# motor_front.net
KiCad netlist of a schematic drawn in EAGLE
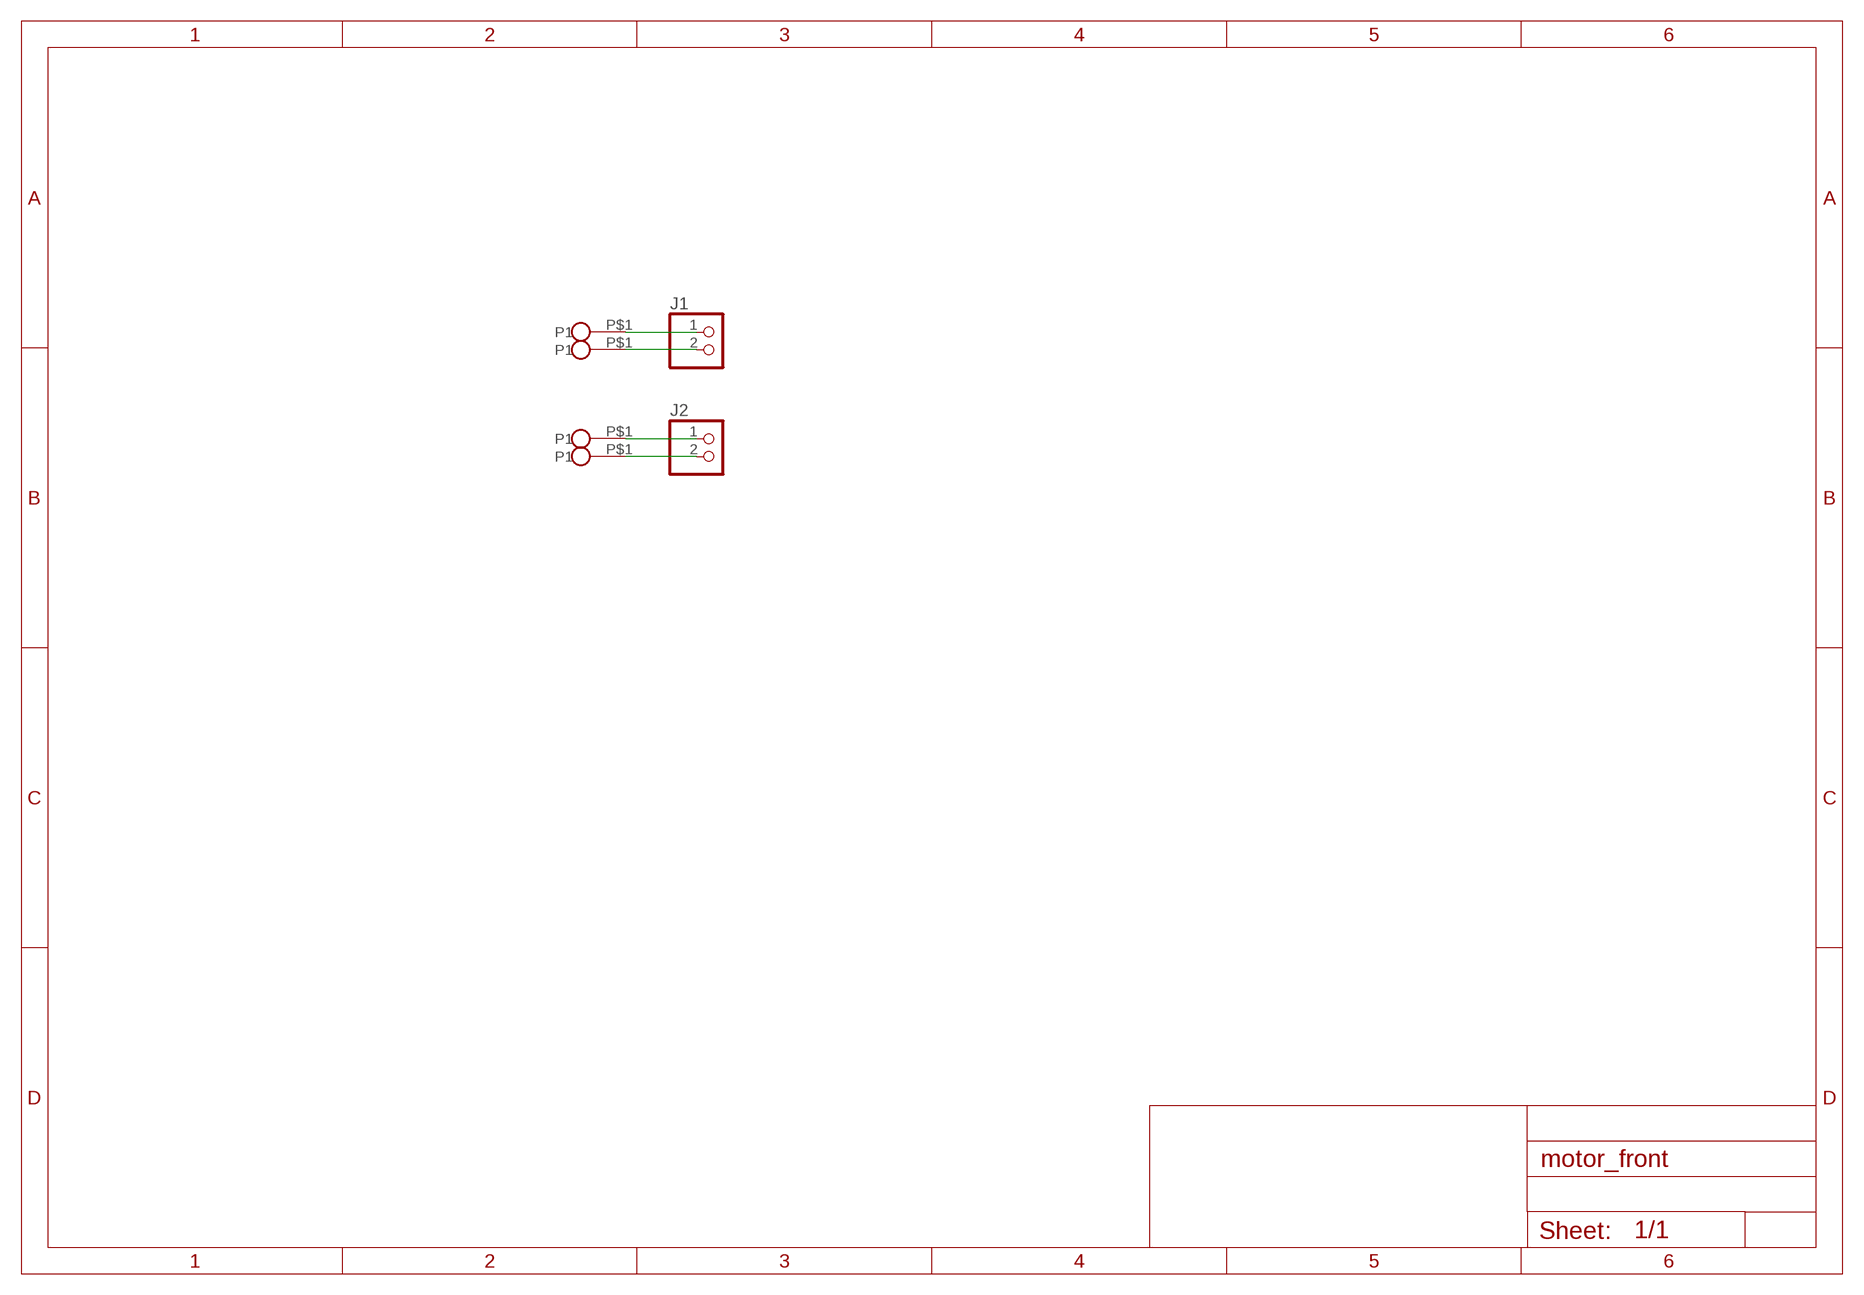
[diagram p0: schematic, sheet 1]

(export (version "E")
  (design (tool "Eeschema 10.0.6"))
  (components
    (comp (ref "J1")
      (value "PINHD-1X2")
      (footprint "eagle-import:1X02")
      (libsource (lib "eagle-import") (part "PINHD-1X2"))
    )
    (comp (ref "J2")
      (value "PINHD-1X2")
      (footprint "eagle-import:1X02")
      (libsource (lib "eagle-import") (part "PINHD-1X2"))
    )
    (comp (ref "U$1")
      (value "BIGHOLE")
      (footprint "eagle-import:BIGHOLE")
      (libsource (lib "eagle-import") (part "BIGHOLE"))
    )
    (comp (ref "U$2")
      (value "BIGHOLE")
      (footprint "eagle-import:BIGHOLE")
      (libsource (lib "eagle-import") (part "BIGHOLE"))
    )
    (comp (ref "U$3")
      (value "BIGHOLE")
      (footprint "eagle-import:BIGHOLE")
      (libsource (lib "eagle-import") (part "BIGHOLE"))
    )
    (comp (ref "U$4")
      (value "BIGHOLE")
      (footprint "eagle-import:BIGHOLE")
      (libsource (lib "eagle-import") (part "BIGHOLE"))
    )
  )
  (nets
    (net (code "1") (name "Net-(U$1-P1)") (class "Default")
      (node (ref "J1") (pin "1") (pinfunction "1_1") (pintype "passive"))
      (node (ref "U$1") (pin "P$1") (pinfunction "P1_P$1") (pintype "bidirectional"))
    )
    (net (code "2") (name "Net-(U$2-P1)") (class "Default")
      (node (ref "J1") (pin "2") (pinfunction "2_2") (pintype "passive"))
      (node (ref "U$2") (pin "P$1") (pinfunction "P1_P$1") (pintype "bidirectional"))
    )
    (net (code "3") (name "Net-(U$3-P1)") (class "Default")
      (node (ref "J2") (pin "2") (pinfunction "2_2") (pintype "passive"))
      (node (ref "U$3") (pin "P$1") (pinfunction "P1_P$1") (pintype "bidirectional"))
    )
    (net (code "4") (name "Net-(U$4-P1)") (class "Default")
      (node (ref "J2") (pin "1") (pinfunction "1_1") (pintype "passive"))
      (node (ref "U$4") (pin "P$1") (pinfunction "P1_P$1") (pintype "bidirectional"))
    )
  )
)
